# TPS6513x.net
KiCad netlist of a schematic drawn in Altium Designer
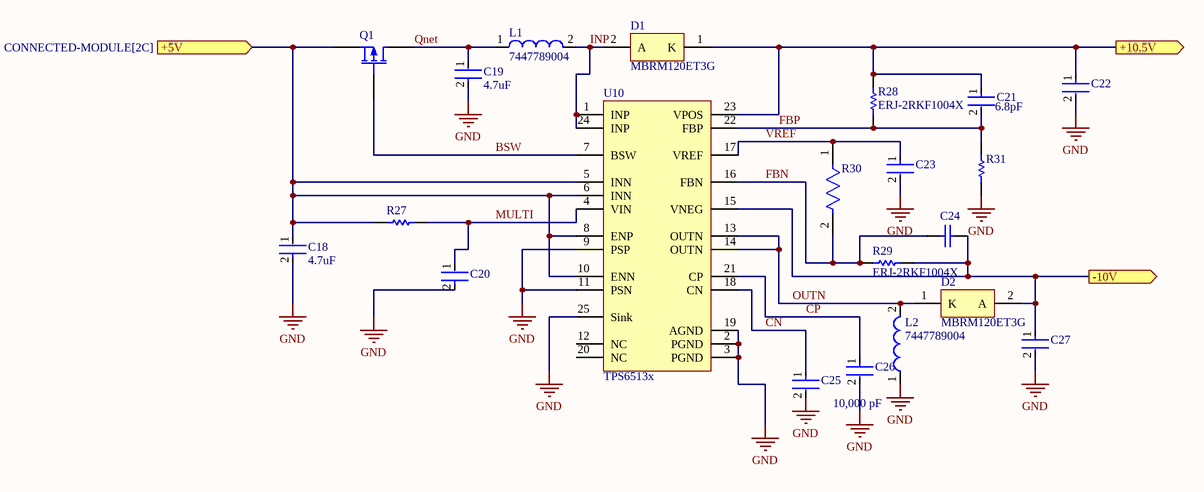
[diagram p0: TPS6513x.SchDoc]

(export (version "E")
  (design (tool "Eeschema 10.0.6"))
  (components
    (comp (ref "C18")
      (value "4.7uF")
      (footprint "FP-GRM15-MFG")
      (description "CAP CER 0.1UF 16V X7R 0402")
      (fields (field (name "MANUFACTURER PART NUMBER") "GRM155R71C104KA88D") (field (name "TOLERANCE") "10%"))
      (libsource (lib "Altium Content Vault") (part "236180d848d6139a670b325ea6854c9"))
    )
    (comp (ref "C19")
      (value "4.7uF")
      (footprint "FP-GRM15-MFG")
      (description "CAP CER 0.1UF 16V X7R 0402")
      (fields (field (name "MANUFACTURER PART NUMBER") "GRM155R71C104KA88D") (field (name "TOLERANCE") "10%"))
      (libsource (lib "Altium Content Vault") (part "236180d848d6139a670b325ea6854c9"))
    )
    (comp (ref "C20")
      (value "GRM155R71C104KA88D")
      (footprint "FP-GRM15-MFG")
      (description "CAP CER 0.1UF 16V X7R 0402")
      (fields
        (field (name "TOLERANCE") "10%")
        (field (name "OCTOPART") "https://octopart.com/grm155r71c104ka88d-murata-196880")
      )
      (libsource (lib "Altium Content Vault") (part "236180d848d6139a670b325ea6854c9"))
    )
    (comp (ref "C21")
      (value "CGA1A2C0G1E6R8D030BA")
      (footprint "885012007027")
      (description "Cap Ceramic 6.8pF 25V C0G 0.5pF Pad SMD 0201 125°C Automotive T/R")
      (fields (field (name "CAPACITANCE") "6.8pF"))
      (libsource (lib "Miscellaneous Devices") (part "b4654b650e69147ec39a6b967a45e02"))
    )
    (comp (ref "C22")
      (value "CL05A226MQ5QUNC")
      (footprint "FP-CL746-IPC_C")
      (description "Cap Ceramic 22uF 6.3V X5R ±20% SMD 0402 +85°C Paper T/R")
      (fields (field (name "TOLERANCE") "20%"))
      (libsource (lib "Altium Content Vault") (part "b4654b650e69147ec39a6b967a45e02"))
    )
    (comp (ref "C23")
      (value "GRM155R71C224KA12D")
      (footprint "FP-GRM155-0_05-IPC_C")
      (description "Chip Multilayer Ceramic Capacitors for General Purpose, 0402, 0.22uF, X7R, 15%, 10%, 16V")
      (fields (field (name "VOLTAGE") "16V") (field (name "TOLERANCE") "10%"))
      (libsource (lib "Altium Content Vault") (part "02cd4be3c70576c341d710602a673aa"))
    )
    (comp (ref "C24")
      (value "GRM1555C1H7R5CA01D")
      (footprint "CAPC1005X55X25LL05T10")
      (fields (field (name "MANUFACTURER") "Murata"))
      (libsource (lib "Altium Content Vault") (part "CAP"))
    )
    (comp (ref "C25")
      (value "GRM155R71H472KA01D")
      (footprint "FP-GRM155-0_05-IPC_B")
      (description "Chip Multilayer Ceramic Capacitors for General Purpose, 0402, 4700pF, X7R, 15%, 10%, 50V")
      (fields (field (name "VOLTAGE") "50V") (field (name "TOLERANCE") "10%"))
      (libsource (lib "Altium Content Vault") (part "02cd4be3c70576c341d710602a673aa"))
    )
    (comp (ref "C26")
      (value "10,000 pF")
      (footprint "Yemet_0603")
      (description "C0402 10,000 pF X7R 5.00% 16 V")
      (fields (field (name "MANUFACTURER PART NUMBER") "C0402C103J4RAC") (field (name "TOLERANCE") "0.05"))
      (libsource (lib "Miscellaneous Devices") (part "b4654b650e69147ec39a6b967a45e02"))
    )
    (comp (ref "C27")
      (value "CL05A226MQ5QUNC")
      (footprint "FP-CL746-IPC_C")
      (description "Cap Ceramic 22uF 6.3V X5R ±20% SMD 0402 +85°C Paper T/R")
      (fields (field (name "TOLERANCE") "20%"))
      (libsource (lib "Altium Content Vault") (part "b4654b650e69147ec39a6b967a45e02"))
    )
    (comp (ref "D1")
      (value "MBRM120ET3G")
      (footprint "ONSC-POWERMITE-2-457-04_D_V")
      (description "Schottky Power Rectifier, 2-Pin Powermite, Pb-Free, Tape and Reel")
      (fields (field (name "MANUFACTURER") "On Semiconductor"))
      (libsource (lib "") (part "ONSC-D-K1A2-2_A_1"))
    )
    (comp (ref "D2")
      (value "MBRM120ET3G")
      (footprint "ONSC-POWERMITE-2-457-04_D_V")
      (description "Schottky Power Rectifier, 2-Pin Powermite, Pb-Free, Tape and Reel")
      (fields (field (name "MANUFACTURER") "On Semiconductor"))
      (libsource (lib "Altium Content Vault") (part "ONSC-D-K1A2-2_A"))
    )
    (comp (ref "L1")
      (value "7447789004")
      (footprint "WE-PD-S-PB")
      (description "SMD-Shielded Power Inductor WE-PD, L=4.70 µH")
      (fields (field (name "MANUFACTURER") "Wuerth Elektronik"))
      (libsource (lib "Altium Content Vault") (part "PAS-IND-INDUCTOR-2"))
    )
    (comp (ref "L2")
      (value "7447789004")
      (footprint "WE-PD-S-PB")
      (description "SMD-Shielded Power Inductor WE-PD, L=4.70 µH")
      (fields (field (name "MANUFACTURER") "Wuerth Elektronik"))
      (libsource (lib "Altium Content Vault") (part "PAS-IND-INDUCTOR-2"))
    )
    (comp (ref "Q1")
      (value "Comment")
      (footprint "PCBComponent_1")
      (description "P-Channel MOSFET")
      (fields (field (name "PUBLISHER") "Altium Limited"))
      (libsource (lib "Miscellaneous Devices") (part "MOSFET-P"))
    )
    (comp (ref "R27")
      (value "ERJ-2RKF1000X")
      (footprint "RESC1005X40X25LL05T05")
      (description "Chip Resistor, 100 Ohm, +/- 1%, 100 mW, -55 to 155 degC, 0402 (1005 Metric), RoHS, Tape and Reel")
      (fields (field (name "MANUFACTURER") "Basic Passives") (field (name "TOLERANCE") "1%"))
      (libsource (lib "Altium Content Vault") (part "RES-2"))
    )
    (comp (ref "R28")
      (value "ERJ-2RKF1004X")
      (footprint "RESC1005X40X25LL05T05")
      (description "Chip Resistor, 1 MOhm, +/- 1%, 100 mW, -55 to 155 degC, 0402 (1005 Metric), RoHS, Tape and Reel")
      (fields (field (name "TOLERANCE") "1%") (field (name "MANUFACTURER") "Basic Passives"))
      (libsource (lib "Altium Content Vault") (part "RES-2"))
    )
    (comp (ref "R29")
      (value "ERJ-2RKF1004X")
      (footprint "RESC1005X40X25LL05T05")
      (description "Chip Resistor, 1 MOhm, +/- 1%, 100 mW, -55 to 155 degC, 0402 (1005 Metric), RoHS, Tape and Reel")
      (fields (field (name "TOLERANCE") "1%") (field (name "MANUFACTURER") "Basic Passives"))
      (libsource (lib "Altium Content Vault") (part "RES-2"))
    )
    (comp (ref "R30")
      (value "CRCW0402121KFKED")
      (footprint "FP-CRCW0402-e3-MFG")
      (description "RES Thick Film, 121kΩ, 1%, 0.063W, 100ppm/°C, 0402")
      (fields (field (name "TOLERANCE") "1%"))
      (libsource (lib "Altium Content Vault") (part "1029c3af85768c4190bb7ad29bc67b5"))
    )
    (comp (ref "R31")
      (value "ERJ-2RKF1303X")
      (footprint "RESC1005X40X25NL05T05")
      (fields (field (name "MANUFACTURER") "Panasonic"))
      (libsource (lib "Altium Content Vault") (part "RES"))
    )
    (comp (ref "U10")
      (value "TPS6513x")
      (footprint "TPS6513final")
      (fields (field (name "PARTNUMBER") "TPS65130RGER") (field (name "MANUFACTURER") "Texas Instruments"))
      (libsource (lib "Buck_and_Inverter") (part "TI-TPS65130RGE24-2450X2450TP"))
    )
  )
  (nets
    (net (code "1") (name "/+5V") (class "Default")
      (node (ref "C18") (pin "1") (pinfunction "1_1") (pintype "passive"))
      (node (ref "Q1") (pin "3") (pinfunction "S_3") (pintype "passive"))
      (node (ref "R27") (pin "1") (pinfunction "1_1") (pintype "passive"))
      (node (ref "U10") (pin "10") (pinfunction "ENN_10") (pintype "passive"))
      (node (ref "U10") (pin "5") (pinfunction "INN_5") (pintype "passive"))
      (node (ref "U10") (pin "6") (pinfunction "INN_6") (pintype "passive"))
      (node (ref "U10") (pin "8") (pinfunction "ENP_8") (pintype "passive"))
    )
    (net (code "2") (name "/+10.5V") (class "Default")
      (node (ref "C21") (pin "1") (pinfunction "1_1") (pintype "passive"))
      (node (ref "C22") (pin "1") (pinfunction "1_1") (pintype "passive"))
      (node (ref "D1") (pin "1") (pinfunction "K_1") (pintype "passive"))
      (node (ref "R28") (pin "2") (pinfunction "2_2") (pintype "passive"))
      (node (ref "U10") (pin "23") (pinfunction "VPOS_23") (pintype "passive"))
    )
    (net (code "3") (name "/-10V") (class "Default")
      (node (ref "C24") (pin "2") (pinfunction "2_2") (pintype "passive"))
      (node (ref "C27") (pin "1") (pinfunction "1_1") (pintype "passive"))
      (node (ref "D2") (pin "2") (pinfunction "A_2") (pintype "passive"))
      (node (ref "R29") (pin "1") (pinfunction "1_1") (pintype "passive"))
      (node (ref "U10") (pin "15") (pinfunction "VNEG_15") (pintype "passive"))
    )
    (net (code "4") (name "/BSW") (class "Default")
      (node (ref "Q1") (pin "2") (pinfunction "G_2") (pintype "passive"))
      (node (ref "U10") (pin "7") (pinfunction "BSW_7") (pintype "passive"))
    )
    (net (code "5") (name "/CN") (class "Default")
      (node (ref "C25") (pin "1") (pinfunction "1_1") (pintype "passive"))
      (node (ref "U10") (pin "18") (pinfunction "CN_18") (pintype "passive"))
    )
    (net (code "6") (name "/CP") (class "Default")
      (node (ref "C26") (pin "1") (pinfunction "1_1") (pintype "passive"))
      (node (ref "U10") (pin "21") (pinfunction "CP_21") (pintype "passive"))
    )
    (net (code "7") (name "/FBN") (class "Default")
      (node (ref "C24") (pin "1") (pinfunction "1_1") (pintype "passive"))
      (node (ref "R29") (pin "2") (pinfunction "2_2") (pintype "passive"))
      (node (ref "R30") (pin "2") (pinfunction "2_2") (pintype "passive"))
      (node (ref "U10") (pin "16") (pinfunction "FBN_16") (pintype "passive"))
    )
    (net (code "8") (name "/FBP") (class "Default")
      (node (ref "C21") (pin "2") (pinfunction "2_2") (pintype "passive"))
      (node (ref "R28") (pin "1") (pinfunction "1_1") (pintype "passive"))
      (node (ref "R31") (pin "2") (pinfunction "2_2") (pintype "passive"))
      (node (ref "U10") (pin "22") (pinfunction "FBP_22") (pintype "passive"))
    )
    (net (code "9") (name "/INP") (class "Default")
      (node (ref "D1") (pin "2") (pinfunction "A_2") (pintype "passive"))
      (node (ref "L1") (pin "2") (pinfunction "2_2") (pintype "passive"))
      (node (ref "U10") (pin "1") (pinfunction "INP_1") (pintype "passive"))
      (node (ref "U10") (pin "24") (pinfunction "INP_24") (pintype "passive"))
    )
    (net (code "10") (name "/MULTI") (class "Default")
      (node (ref "C20") (pin "1") (pinfunction "1_1") (pintype "passive"))
      (node (ref "R27") (pin "2") (pinfunction "2_2") (pintype "passive"))
      (node (ref "U10") (pin "4") (pinfunction "VIN_4") (pintype "passive"))
    )
    (net (code "11") (name "/OUTN") (class "Default")
      (node (ref "D2") (pin "1") (pinfunction "K_1") (pintype "passive"))
      (node (ref "L2") (pin "2") (pinfunction "2_2") (pintype "passive"))
      (node (ref "U10") (pin "13") (pinfunction "OUTN_13") (pintype "passive"))
      (node (ref "U10") (pin "14") (pinfunction "OUTN_14") (pintype "passive"))
    )
    (net (code "12") (name "/Qnet") (class "Default")
      (node (ref "C19") (pin "1") (pinfunction "1_1") (pintype "passive"))
      (node (ref "L1") (pin "1") (pinfunction "1_1") (pintype "passive"))
      (node (ref "Q1") (pin "1") (pinfunction "D_1") (pintype "passive"))
    )
    (net (code "13") (name "/VREF") (class "Default")
      (node (ref "C23") (pin "1") (pinfunction "1_1") (pintype "passive"))
      (node (ref "R30") (pin "1") (pinfunction "1_1") (pintype "passive"))
      (node (ref "U10") (pin "17") (pinfunction "VREF_17") (pintype "passive"))
    )
    (net (code "14") (name "GND") (class "Default")
      (node (ref "C18") (pin "2") (pinfunction "2_2") (pintype "passive"))
      (node (ref "C19") (pin "2") (pinfunction "2_2") (pintype "passive"))
      (node (ref "C20") (pin "2") (pinfunction "2_2") (pintype "passive"))
      (node (ref "C22") (pin "2") (pinfunction "2_2") (pintype "passive"))
      (node (ref "C23") (pin "2") (pinfunction "2_2") (pintype "passive"))
      (node (ref "C25") (pin "2") (pinfunction "2_2") (pintype "passive"))
      (node (ref "C26") (pin "2") (pinfunction "2_2") (pintype "passive"))
      (node (ref "C27") (pin "2") (pinfunction "2_2") (pintype "passive"))
      (node (ref "L2") (pin "1") (pinfunction "1_1") (pintype "passive"))
      (node (ref "R31") (pin "1") (pinfunction "1_1") (pintype "passive"))
      (node (ref "U10") (pin "11") (pinfunction "PSN_11") (pintype "passive"))
      (node (ref "U10") (pin "19") (pinfunction "AGND_19") (pintype "passive"))
      (node (ref "U10") (pin "2") (pinfunction "PGND_2") (pintype "passive"))
      (node (ref "U10") (pin "25") (pinfunction "Sink_25") (pintype "passive"))
      (node (ref "U10") (pin "3") (pinfunction "PGND_3") (pintype "passive"))
      (node (ref "U10") (pin "9") (pinfunction "PSP_9") (pintype "passive"))
    )
    (net (code "15") (name "unconnected-(U10-NC-Pad12)") (class "Default")
      (node (ref "U10") (pin "12") (pinfunction "NC_12") (pintype "passive"))
    )
    (net (code "16") (name "unconnected-(U10-NC-Pad20)") (class "Default")
      (node (ref "U10") (pin "20") (pinfunction "NC_20") (pintype "passive"))
    )
  )
)
